# Pixracer_V1_FMU_Alternative_3.net
KiCad netlist of a schematic drawn in Altium Designer
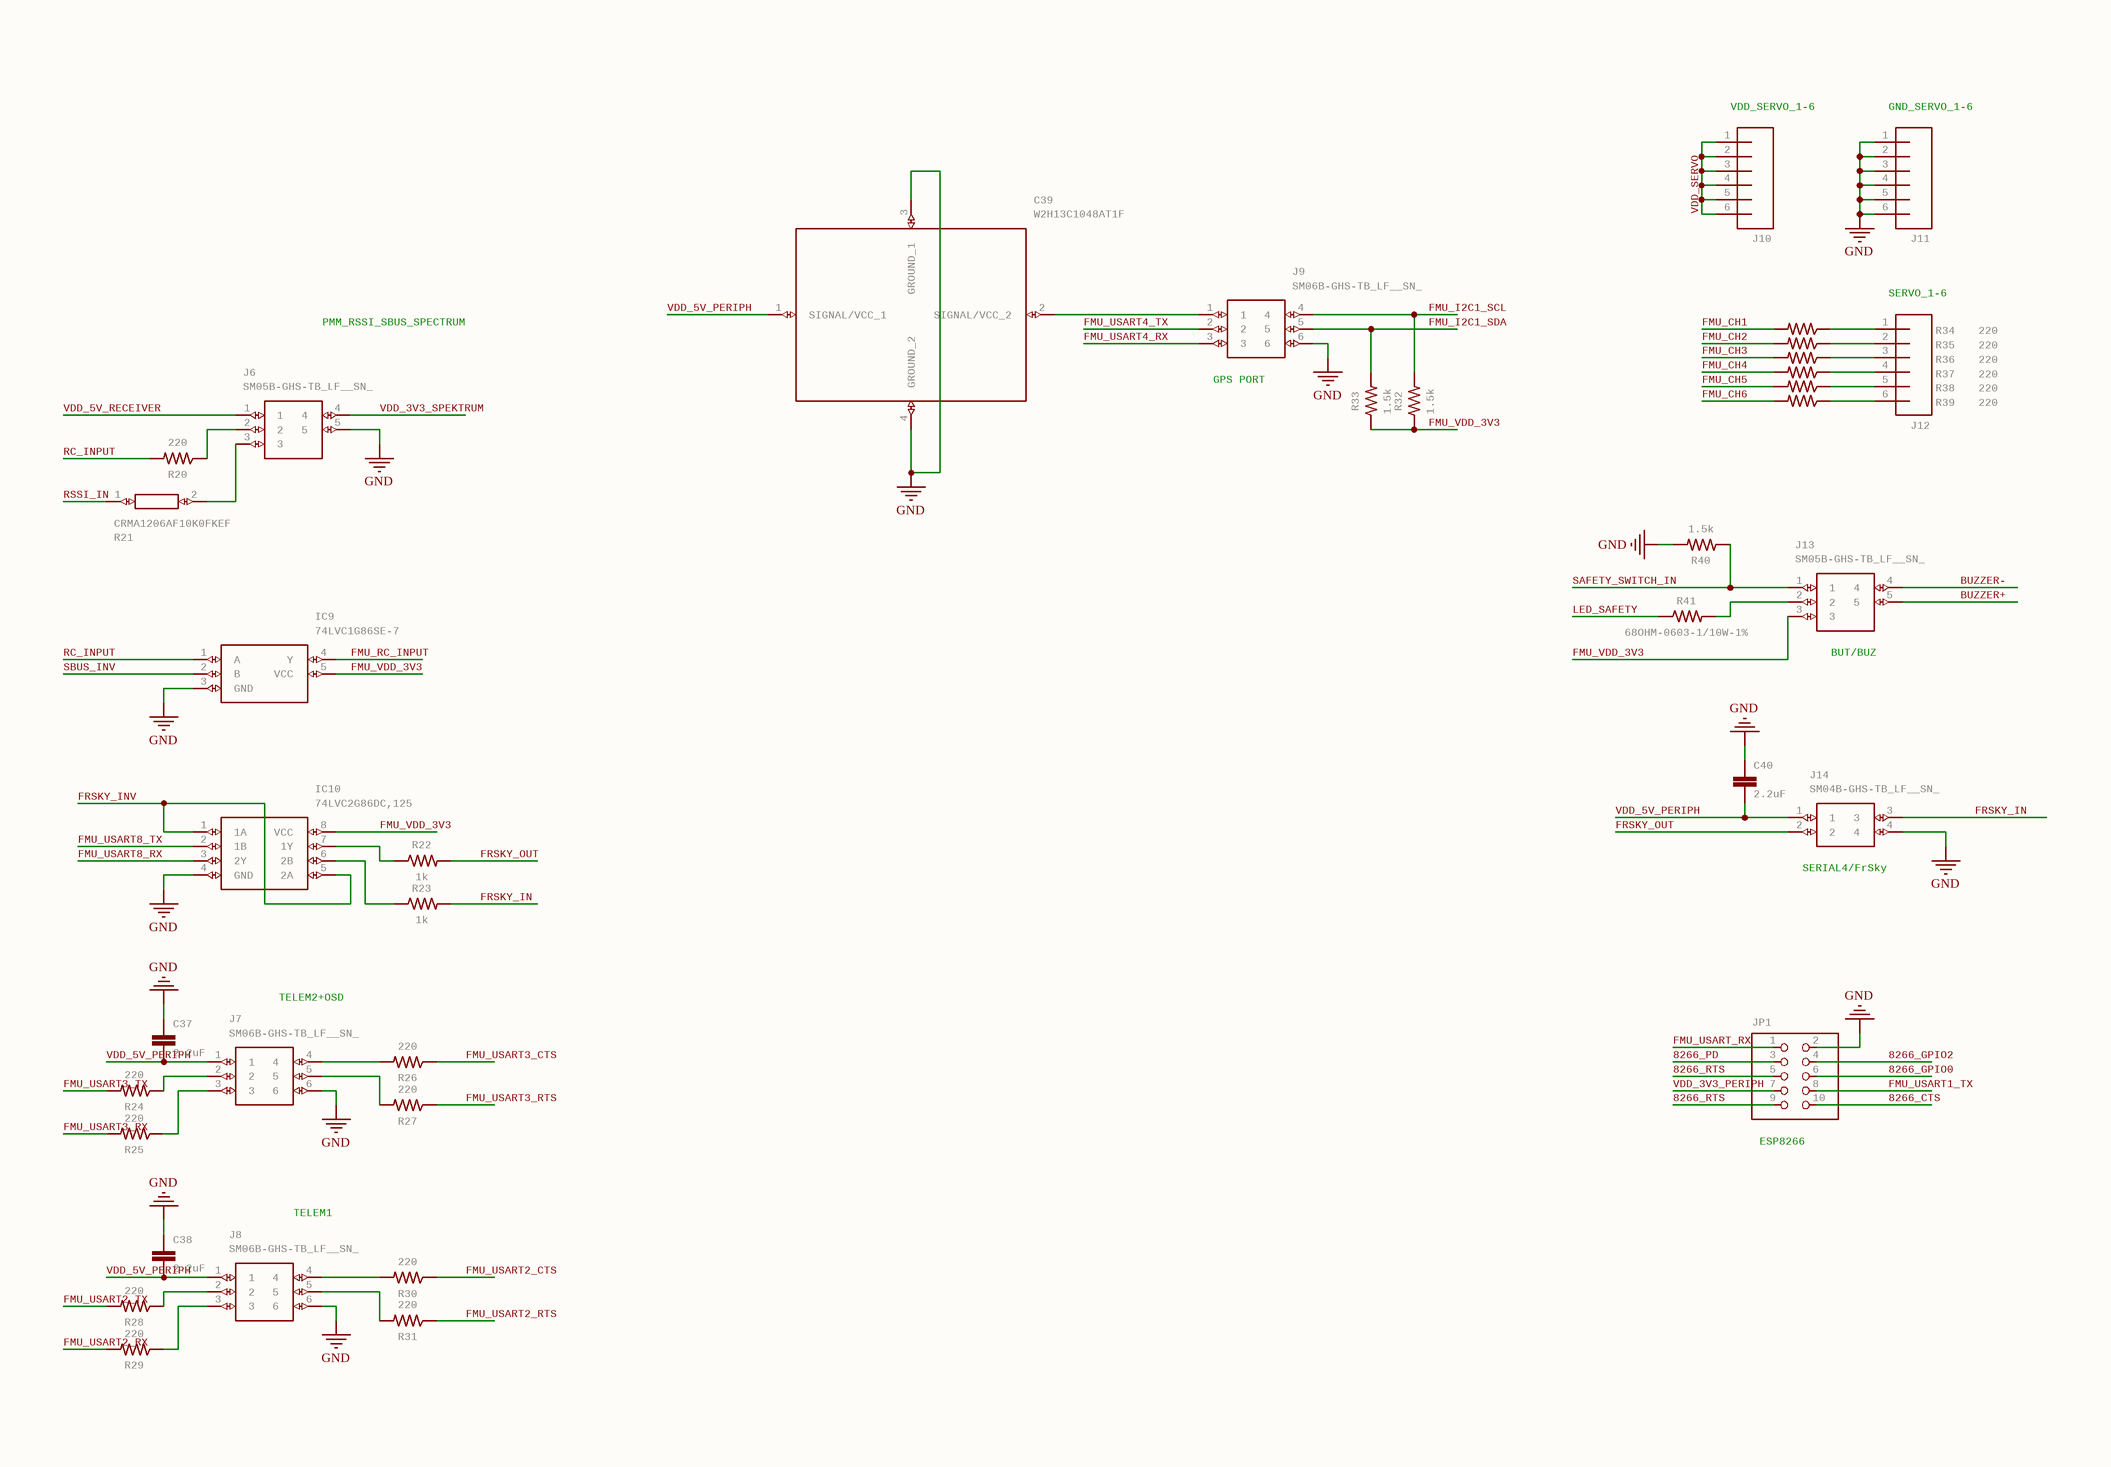
[diagram p0: Pixracer_V1_FMU_Alternative_3.SchDoc]

(export (version "E")
  (design (tool "Eeschema 10.0.6"))
  (components
    (comp (ref "C37")
      (value "2.2uF")
      (footprint "1206")
      (libsource (lib "SparkFun-Capacitors") (part "2.2UF-1206-50V-10%"))
    )
    (comp (ref "C38")
      (value "2.2uF")
      (footprint "1206")
      (libsource (lib "SparkFun-Capacitors") (part "2.2UF-1206-50V-10%"))
    )
    (comp (ref "C39")
      (value "W2H13C1048AT1F")
      (footprint "W2H13C1048AT1A")
      (description "Feed Through Capacitors 25volt 0.1uF X7R")
      (fields (field (name "MOUSER_PART_NUMBER") "581-W2H13C1048AT1F"))
      (libsource (lib "SamacSys_Parts") (part "W2H13C1048AT1F"))
    )
    (comp (ref "C40")
      (value "2.2uF")
      (footprint "1206")
      (libsource (lib "SparkFun-Capacitors") (part "2.2UF-1206-50V-10%"))
    )
    (comp (ref "IC9")
      (value "74LVC1G86SE-7")
      (footprint "SOT65P210X110-5N")
      (description "DiodesZetex 74LVC1G86SE-7, XOR 2 Input XOR, 1.65  5.5 V, 5-Pin SOT-353")
      (fields (field (name "MOUSER_PART_NUMBER") "621-74LVC1G86SE-7"))
      (libsource (lib "SamacSys_Parts") (part "74LVC1G86SE-7"))
    )
    (comp (ref "IC10")
      (value "74LVC2G86DC,125")
      (footprint "SOP50P310X100-8N")
      (description "74LVC2G86 - Dual 2-input EXCLUSIVE-OR gate")
      (fields (field (name "MOUSER_PART_NUMBER") "771-LVC2G86DC125"))
      (libsource (lib "SamacSys_Parts") (part "74LVC2G86DC,125"))
    )
    (comp (ref "J6")
      (value "SM05B-GHS-TB_LF__SN_")
      (footprint "SM05B-GHS-TB")
      (description "JST GH Series, 1.25mm Pitch 5 Way Right Angle PCB Header, Solder Termination, 1A")
      (fields
        (field (name "MANUFACTURER_PART_NUMBER") "SM05B-GHS-TB(LF)(SN)")
        (field (name "RS_PART_NUMBER") "7521807P")
      )
      (libsource (lib "SamacSys_Parts") (part "SM05B-GHS-TB_LF__SN_"))
    )
    (comp (ref "J7")
      (value "SM06B-GHS-TB_LF__SN_")
      (footprint "SM06B-GHS-TB")
      (fields
        (field (name "MANUFACTURER_PART_NUMBER") "SM06B-GHS-TB(LF)(SN)")
        (field (name "RS_PART_NUMBER") "7521800P")
      )
      (libsource (lib "SamacSys_Parts") (part "SM06B-GHS-TB_LF__SN_"))
    )
    (comp (ref "J8")
      (value "SM06B-GHS-TB_LF__SN_")
      (footprint "SM06B-GHS-TB")
      (fields
        (field (name "MANUFACTURER_PART_NUMBER") "SM06B-GHS-TB(LF)(SN)")
        (field (name "RS_PART_NUMBER") "7521800P")
      )
      (libsource (lib "SamacSys_Parts") (part "SM06B-GHS-TB_LF__SN_"))
    )
    (comp (ref "J9")
      (value "SM06B-GHS-TB_LF__SN_")
      (footprint "SM06B-GHS-TB")
      (fields
        (field (name "MANUFACTURER_PART_NUMBER") "SM06B-GHS-TB(LF)(SN)")
        (field (name "RS_PART_NUMBER") "7521800P")
      )
      (libsource (lib "SamacSys_Parts") (part "SM06B-GHS-TB_LF__SN_"))
    )
    (comp (ref "J10")
      (value "CONN_06NO_SILK_NO_POP")
      (footprint "1X06_NO_SILK")
      (libsource (lib "SparkFun-Connectors") (part "CONN_06NO_SILK_NO_POP"))
    )
    (comp (ref "J11")
      (value "CONN_06NO_SILK_NO_POP")
      (footprint "1X06_NO_SILK")
      (libsource (lib "SparkFun-Connectors") (part "CONN_06NO_SILK_NO_POP"))
    )
    (comp (ref "J12")
      (value "CONN_06NO_SILK_NO_POP")
      (footprint "1X06_NO_SILK")
      (libsource (lib "SparkFun-Connectors") (part "CONN_06NO_SILK_NO_POP"))
    )
    (comp (ref "J13")
      (value "SM05B-GHS-TB_LF__SN_")
      (footprint "SM05B-GHS-TB")
      (description "JST GH Series, 1.25mm Pitch 5 Way Right Angle PCB Header, Solder Termination, 1A")
      (fields
        (field (name "MANUFACTURER_PART_NUMBER") "SM05B-GHS-TB(LF)(SN)")
        (field (name "RS_PART_NUMBER") "7521807P")
      )
      (libsource (lib "SamacSys_Parts") (part "SM05B-GHS-TB_LF__SN_"))
    )
    (comp (ref "J14")
      (value "SM04B-GHS-TB_LF__SN_")
      (footprint "SM04B-GHS-TB")
      (description "JST GH Series, 1.25mm Pitch 4 Way Right Angle PCB Header, Solder Termination, 1A")
      (fields
        (field (name "MANUFACTURER_PART_NUMBER") "SM04B-GHS-TB(LF)(SN)")
        (field (name "RS_PART_NUMBER") "7521797P")
      )
      (libsource (lib "SamacSys_Parts") (part "SM04B-GHS-TB_LF__SN_"))
    )
    (comp (ref "JP1")
      (value "PINHD-2X5")
      (footprint "2X05")
      (description "PIN HEADER")
      (fields (field (name "LIBRARYNAME") "pinhead"))
      (libsource (lib "pinhead") (part "PINHD-2X5"))
    )
    (comp (ref "R20")
      (value "220")
      (footprint "0603")
      (libsource (lib "SparkFun-Resistors") (part "220OHM-0603-1/10W-1%"))
    )
    (comp (ref "R21")
      (value "CRMA1206AF10K0FKEF")
      (footprint "RESC3216X74N")
      (description "Thick Film Resistors - SMD 0.30W 10Kohm 1% AEC-Q200")
      (fields (field (name "MOUSER_PART_NUMBER") "71-CRMA1206AF10K0FKF"))
      (libsource (lib "SamacSys_Parts") (part "CRMA1206AF10K0FKEF"))
    )
    (comp (ref "R22")
      (value "1k")
      (footprint "0603")
      (libsource (lib "SparkFun-Resistors") (part "1KOHM-0603-1/10W-1%"))
    )
    (comp (ref "R23")
      (value "1k")
      (footprint "0603")
      (libsource (lib "SparkFun-Resistors") (part "1KOHM-0603-1/10W-1%"))
    )
    (comp (ref "R24")
      (value "220")
      (footprint "0603")
      (libsource (lib "SparkFun-Resistors") (part "220OHM-0603-1/10W-1%"))
    )
    (comp (ref "R25")
      (value "220")
      (footprint "0603")
      (libsource (lib "SparkFun-Resistors") (part "220OHM-0603-1/10W-1%"))
    )
    (comp (ref "R26")
      (value "220")
      (footprint "0603")
      (libsource (lib "SparkFun-Resistors") (part "220OHM-0603-1/10W-1%"))
    )
    (comp (ref "R27")
      (value "220")
      (footprint "0603")
      (libsource (lib "SparkFun-Resistors") (part "220OHM-0603-1/10W-1%"))
    )
    (comp (ref "R28")
      (value "220")
      (footprint "0603")
      (libsource (lib "SparkFun-Resistors") (part "220OHM-0603-1/10W-1%"))
    )
    (comp (ref "R29")
      (value "220")
      (footprint "0603")
      (libsource (lib "SparkFun-Resistors") (part "220OHM-0603-1/10W-1%"))
    )
    (comp (ref "R30")
      (value "220")
      (footprint "0603")
      (libsource (lib "SparkFun-Resistors") (part "220OHM-0603-1/10W-1%"))
    )
    (comp (ref "R31")
      (value "220")
      (footprint "0603")
      (libsource (lib "SparkFun-Resistors") (part "220OHM-0603-1/10W-1%"))
    )
    (comp (ref "R32")
      (value "1.5k")
      (footprint "0603")
      (libsource (lib "SparkFun-Resistors") (part "1.5KOHM-0603-1/10W-1%"))
    )
    (comp (ref "R33")
      (value "1.5k")
      (footprint "0603")
      (libsource (lib "SparkFun-Resistors") (part "1.5KOHM-0603-1/10W-1%"))
    )
    (comp (ref "R34")
      (value "220")
      (footprint "0603")
      (libsource (lib "SparkFun-Resistors") (part "220OHM-0603-1/10W-1%"))
    )
    (comp (ref "R35")
      (value "220")
      (footprint "0603")
      (libsource (lib "SparkFun-Resistors") (part "220OHM-0603-1/10W-1%"))
    )
    (comp (ref "R36")
      (value "220")
      (footprint "0603")
      (libsource (lib "SparkFun-Resistors") (part "220OHM-0603-1/10W-1%"))
    )
    (comp (ref "R37")
      (value "220")
      (footprint "0603")
      (libsource (lib "SparkFun-Resistors") (part "220OHM-0603-1/10W-1%"))
    )
    (comp (ref "R38")
      (value "220")
      (footprint "0603")
      (libsource (lib "SparkFun-Resistors") (part "220OHM-0603-1/10W-1%"))
    )
    (comp (ref "R39")
      (value "220")
      (footprint "0603")
      (libsource (lib "SparkFun-Resistors") (part "220OHM-0603-1/10W-1%"))
    )
    (comp (ref "R40")
      (value "1.5k")
      (footprint "0603")
      (libsource (lib "SparkFun-Resistors") (part "1.5KOHM-0603-1/10W-1%"))
    )
    (comp (ref "R41")
      (value "68OHM-0603-1/10W-1%")
      (footprint "0603")
      (libsource (lib "SparkFun-Resistors") (part "68OHM-0603-1/10W-1%"))
    )
  )
  (nets
    (net (code "1") (name "/8266_CTS") (class "Default")
      (node (ref "JP1") (pin "10") (pinfunction "10_10") (pintype "passive"))
    )
    (net (code "2") (name "/8266_GPIO0") (class "Default")
      (node (ref "JP1") (pin "6") (pinfunction "6_6") (pintype "passive"))
    )
    (net (code "3") (name "/8266_GPIO2") (class "Default")
      (node (ref "JP1") (pin "4") (pinfunction "4_4") (pintype "passive"))
    )
    (net (code "4") (name "/8266_PD") (class "Default")
      (node (ref "JP1") (pin "3") (pinfunction "3_3") (pintype "passive"))
    )
    (net (code "5") (name "/8266_RTS") (class "Default")
      (node (ref "JP1") (pin "5") (pinfunction "5_5") (pintype "passive"))
      (node (ref "JP1") (pin "9") (pinfunction "9_9") (pintype "passive"))
    )
    (net (code "6") (name "/BUZZER+") (class "Default")
      (node (ref "J13") (pin "5") (pinfunction "5_5") (pintype "bidirectional"))
    )
    (net (code "7") (name "/BUZZER-") (class "Default")
      (node (ref "J13") (pin "4") (pinfunction "4_4") (pintype "bidirectional"))
    )
    (net (code "8") (name "/FMU_CH1") (class "Default")
      (node (ref "R34") (pin "2") (pinfunction "2_2") (pintype "passive"))
    )
    (net (code "9") (name "/FMU_CH2") (class "Default")
      (node (ref "R35") (pin "2") (pinfunction "2_2") (pintype "passive"))
    )
    (net (code "10") (name "/FMU_CH3") (class "Default")
      (node (ref "R36") (pin "2") (pinfunction "2_2") (pintype "passive"))
    )
    (net (code "11") (name "/FMU_CH4") (class "Default")
      (node (ref "R37") (pin "2") (pinfunction "2_2") (pintype "passive"))
    )
    (net (code "12") (name "/FMU_CH5") (class "Default")
      (node (ref "R38") (pin "2") (pinfunction "2_2") (pintype "passive"))
    )
    (net (code "13") (name "/FMU_CH6") (class "Default")
      (node (ref "R39") (pin "2") (pinfunction "2_2") (pintype "passive"))
    )
    (net (code "14") (name "/FMU_I2C1_SCL") (class "Default")
      (node (ref "J9") (pin "4") (pinfunction "4_4") (pintype "bidirectional"))
      (node (ref "R32") (pin "2") (pinfunction "2_2") (pintype "passive"))
    )
    (net (code "15") (name "/FMU_I2C1_SDA") (class "Default")
      (node (ref "J9") (pin "5") (pinfunction "5_5") (pintype "bidirectional"))
      (node (ref "R33") (pin "2") (pinfunction "2_2") (pintype "passive"))
    )
    (net (code "16") (name "/FMU_RC_INPUT") (class "Default")
      (node (ref "IC9") (pin "4") (pinfunction "Y_4") (pintype "bidirectional"))
    )
    (net (code "17") (name "/FMU_USART1_TX") (class "Default")
      (node (ref "JP1") (pin "8") (pinfunction "8_8") (pintype "passive"))
    )
    (net (code "18") (name "/FMU_USART2_CTS") (class "Default")
      (node (ref "R30") (pin "1") (pinfunction "1_1") (pintype "passive"))
    )
    (net (code "19") (name "/FMU_USART2_RTS") (class "Default")
      (node (ref "R31") (pin "1") (pinfunction "1_1") (pintype "passive"))
    )
    (net (code "20") (name "/FMU_USART2_RX") (class "Default")
      (node (ref "R29") (pin "2") (pinfunction "2_2") (pintype "passive"))
    )
    (net (code "21") (name "/FMU_USART2_TX") (class "Default")
      (node (ref "R28") (pin "2") (pinfunction "2_2") (pintype "passive"))
    )
    (net (code "22") (name "/FMU_USART3_CTS") (class "Default")
      (node (ref "R26") (pin "1") (pinfunction "1_1") (pintype "passive"))
    )
    (net (code "23") (name "/FMU_USART3_RTS") (class "Default")
      (node (ref "R27") (pin "1") (pinfunction "1_1") (pintype "passive"))
    )
    (net (code "24") (name "/FMU_USART3_RX") (class "Default")
      (node (ref "R25") (pin "2") (pinfunction "2_2") (pintype "passive"))
    )
    (net (code "25") (name "/FMU_USART3_TX") (class "Default")
      (node (ref "R24") (pin "2") (pinfunction "2_2") (pintype "passive"))
    )
    (net (code "26") (name "/FMU_USART4_RX") (class "Default")
      (node (ref "J9") (pin "3") (pinfunction "3_3") (pintype "bidirectional"))
    )
    (net (code "27") (name "/FMU_USART4_TX") (class "Default")
      (node (ref "J9") (pin "2") (pinfunction "2_2") (pintype "bidirectional"))
    )
    (net (code "28") (name "/FMU_USART8_RX") (class "Default")
      (node (ref "IC10") (pin "3") (pinfunction "2Y_3") (pintype "bidirectional"))
    )
    (net (code "29") (name "/FMU_USART8_TX") (class "Default")
      (node (ref "IC10") (pin "2") (pinfunction "1B_2") (pintype "bidirectional"))
    )
    (net (code "30") (name "/FMU_USART_RX") (class "Default")
      (node (ref "JP1") (pin "1") (pinfunction "1_1") (pintype "passive"))
    )
    (net (code "31") (name "/FMU_VDD_3V3") (class "Default")
      (node (ref "IC10") (pin "8") (pinfunction "VCC_8") (pintype "bidirectional"))
      (node (ref "IC9") (pin "5") (pinfunction "VCC_5") (pintype "bidirectional"))
      (node (ref "J13") (pin "3") (pinfunction "3_3") (pintype "bidirectional"))
      (node (ref "R32") (pin "1") (pinfunction "1_1") (pintype "passive"))
      (node (ref "R33") (pin "1") (pinfunction "1_1") (pintype "passive"))
    )
    (net (code "32") (name "/FRSKY_IN") (class "Default")
      (node (ref "J14") (pin "3") (pinfunction "3_3") (pintype "bidirectional"))
      (node (ref "R23") (pin "2") (pinfunction "2_2") (pintype "passive"))
    )
    (net (code "33") (name "/FRSKY_INV") (class "Default")
      (node (ref "IC10") (pin "1") (pinfunction "1A_1") (pintype "bidirectional"))
      (node (ref "IC10") (pin "5") (pinfunction "2A_5") (pintype "bidirectional"))
    )
    (net (code "34") (name "/FRSKY_OUT") (class "Default")
      (node (ref "J14") (pin "2") (pinfunction "2_2") (pintype "bidirectional"))
      (node (ref "R22") (pin "2") (pinfunction "2_2") (pintype "passive"))
    )
    (net (code "35") (name "/LED_SAFETY") (class "Default")
      (node (ref "R41") (pin "1") (pinfunction "1_1") (pintype "passive"))
    )
    (net (code "36") (name "/RC_INPUT") (class "Default")
      (node (ref "IC9") (pin "1") (pinfunction "A_1") (pintype "bidirectional"))
      (node (ref "R20") (pin "2") (pinfunction "2_2") (pintype "passive"))
    )
    (net (code "37") (name "/RSSI_IN") (class "Default")
      (node (ref "R21") (pin "1") (pinfunction "1_1") (pintype "bidirectional"))
    )
    (net (code "38") (name "/SAFETY_SWITCH_IN") (class "Default")
      (node (ref "J13") (pin "1") (pinfunction "1_1") (pintype "bidirectional"))
      (node (ref "R40") (pin "1") (pinfunction "1_1") (pintype "passive"))
    )
    (net (code "39") (name "/SBUS_INV") (class "Default")
      (node (ref "IC9") (pin "2") (pinfunction "B_2") (pintype "bidirectional"))
    )
    (net (code "40") (name "/VDD_3V3_PERIPH") (class "Default")
      (node (ref "JP1") (pin "7") (pinfunction "7_7") (pintype "passive"))
    )
    (net (code "41") (name "/VDD_3V3_SPEKTRUM") (class "Default")
      (node (ref "J6") (pin "4") (pinfunction "4_4") (pintype "bidirectional"))
    )
    (net (code "42") (name "/VDD_5V_PERIPH") (class "Default")
      (node (ref "C37") (pin "2") (pinfunction "2_2") (pintype "passive"))
      (node (ref "C38") (pin "2") (pinfunction "2_2") (pintype "passive"))
      (node (ref "C39") (pin "1") (pinfunction "SIGNAL/VCC_1_1") (pintype "bidirectional"))
      (node (ref "C40") (pin "2") (pinfunction "2_2") (pintype "passive"))
      (node (ref "J14") (pin "1") (pinfunction "1_1") (pintype "bidirectional"))
      (node (ref "J7") (pin "1") (pinfunction "1_1") (pintype "bidirectional"))
      (node (ref "J8") (pin "1") (pinfunction "1_1") (pintype "bidirectional"))
    )
    (net (code "43") (name "/VDD_5V_RECEIVER") (class "Default")
      (node (ref "J6") (pin "1") (pinfunction "1_1") (pintype "bidirectional"))
    )
    (net (code "44") (name "/VDD_SERVO") (class "Default")
      (node (ref "J10") (pin "1") (pinfunction "1_1") (pintype "passive"))
      (node (ref "J10") (pin "2") (pinfunction "2_2") (pintype "passive"))
      (node (ref "J10") (pin "3") (pinfunction "3_3") (pintype "passive"))
      (node (ref "J10") (pin "4") (pinfunction "4_4") (pintype "passive"))
      (node (ref "J10") (pin "5") (pinfunction "5_5") (pintype "passive"))
      (node (ref "J10") (pin "6") (pinfunction "6_6") (pintype "passive"))
    )
    (net (code "45") (name "GND") (class "Default")
      (node (ref "C37") (pin "1") (pinfunction "1_1") (pintype "passive"))
      (node (ref "C38") (pin "1") (pinfunction "1_1") (pintype "passive"))
      (node (ref "C39") (pin "3") (pinfunction "GROUND_1_3") (pintype "bidirectional"))
      (node (ref "C39") (pin "4") (pinfunction "GROUND_2_4") (pintype "bidirectional"))
      (node (ref "C40") (pin "1") (pinfunction "1_1") (pintype "passive"))
      (node (ref "IC10") (pin "4") (pinfunction "GND_4") (pintype "bidirectional"))
      (node (ref "IC9") (pin "3") (pinfunction "GND_3") (pintype "bidirectional"))
      (node (ref "J11") (pin "1") (pinfunction "1_1") (pintype "passive"))
      (node (ref "J11") (pin "2") (pinfunction "2_2") (pintype "passive"))
      (node (ref "J11") (pin "3") (pinfunction "3_3") (pintype "passive"))
      (node (ref "J11") (pin "4") (pinfunction "4_4") (pintype "passive"))
      (node (ref "J11") (pin "5") (pinfunction "5_5") (pintype "passive"))
      (node (ref "J11") (pin "6") (pinfunction "6_6") (pintype "passive"))
      (node (ref "J14") (pin "4") (pinfunction "4_4") (pintype "bidirectional"))
      (node (ref "J6") (pin "5") (pinfunction "5_5") (pintype "bidirectional"))
      (node (ref "J7") (pin "6") (pinfunction "6_6") (pintype "bidirectional"))
      (node (ref "J8") (pin "6") (pinfunction "6_6") (pintype "bidirectional"))
      (node (ref "J9") (pin "6") (pinfunction "6_6") (pintype "bidirectional"))
      (node (ref "JP1") (pin "2") (pinfunction "2_2") (pintype "passive"))
      (node (ref "R40") (pin "2") (pinfunction "2_2") (pintype "passive"))
    )
    (net (code "46") (name "Net-(C39-SIGNAL{slash}VCC_2)") (class "Default")
      (node (ref "C39") (pin "2") (pinfunction "SIGNAL/VCC_2_2") (pintype "bidirectional"))
      (node (ref "J9") (pin "1") (pinfunction "1_1") (pintype "bidirectional"))
    )
    (net (code "47") (name "Net-(IC10-1Y)") (class "Default")
      (node (ref "IC10") (pin "7") (pinfunction "1Y_7") (pintype "bidirectional"))
      (node (ref "R22") (pin "1") (pinfunction "1_1") (pintype "passive"))
    )
    (net (code "48") (name "Net-(IC10-2B)") (class "Default")
      (node (ref "IC10") (pin "6") (pinfunction "2B_6") (pintype "bidirectional"))
      (node (ref "R23") (pin "1") (pinfunction "1_1") (pintype "passive"))
    )
    (net (code "49") (name "Net-(J6-Pad2)") (class "Default")
      (node (ref "J6") (pin "2") (pinfunction "2_2") (pintype "bidirectional"))
      (node (ref "R20") (pin "1") (pinfunction "1_1") (pintype "passive"))
    )
    (net (code "50") (name "Net-(J6-Pad3)") (class "Default")
      (node (ref "J6") (pin "3") (pinfunction "3_3") (pintype "bidirectional"))
      (node (ref "R21") (pin "2") (pinfunction "2_2") (pintype "bidirectional"))
    )
    (net (code "51") (name "Net-(J7-Pad2)") (class "Default")
      (node (ref "J7") (pin "2") (pinfunction "2_2") (pintype "bidirectional"))
      (node (ref "R24") (pin "1") (pinfunction "1_1") (pintype "passive"))
    )
    (net (code "52") (name "Net-(J7-Pad3)") (class "Default")
      (node (ref "J7") (pin "3") (pinfunction "3_3") (pintype "bidirectional"))
      (node (ref "R25") (pin "1") (pinfunction "1_1") (pintype "passive"))
    )
    (net (code "53") (name "Net-(J7-Pad4)") (class "Default")
      (node (ref "J7") (pin "4") (pinfunction "4_4") (pintype "bidirectional"))
      (node (ref "R26") (pin "2") (pinfunction "2_2") (pintype "passive"))
    )
    (net (code "54") (name "Net-(J7-Pad5)") (class "Default")
      (node (ref "J7") (pin "5") (pinfunction "5_5") (pintype "bidirectional"))
      (node (ref "R27") (pin "2") (pinfunction "2_2") (pintype "passive"))
    )
    (net (code "55") (name "Net-(J8-Pad2)") (class "Default")
      (node (ref "J8") (pin "2") (pinfunction "2_2") (pintype "bidirectional"))
      (node (ref "R28") (pin "1") (pinfunction "1_1") (pintype "passive"))
    )
    (net (code "56") (name "Net-(J8-Pad3)") (class "Default")
      (node (ref "J8") (pin "3") (pinfunction "3_3") (pintype "bidirectional"))
      (node (ref "R29") (pin "1") (pinfunction "1_1") (pintype "passive"))
    )
    (net (code "57") (name "Net-(J8-Pad4)") (class "Default")
      (node (ref "J8") (pin "4") (pinfunction "4_4") (pintype "bidirectional"))
      (node (ref "R30") (pin "2") (pinfunction "2_2") (pintype "passive"))
    )
    (net (code "58") (name "Net-(J8-Pad5)") (class "Default")
      (node (ref "J8") (pin "5") (pinfunction "5_5") (pintype "bidirectional"))
      (node (ref "R31") (pin "2") (pinfunction "2_2") (pintype "passive"))
    )
    (net (code "59") (name "Net-(J12-Pad1)") (class "Default")
      (node (ref "J12") (pin "1") (pinfunction "1_1") (pintype "passive"))
      (node (ref "R34") (pin "1") (pinfunction "1_1") (pintype "passive"))
    )
    (net (code "60") (name "Net-(J12-Pad2)") (class "Default")
      (node (ref "J12") (pin "2") (pinfunction "2_2") (pintype "passive"))
      (node (ref "R35") (pin "1") (pinfunction "1_1") (pintype "passive"))
    )
    (net (code "61") (name "Net-(J12-Pad3)") (class "Default")
      (node (ref "J12") (pin "3") (pinfunction "3_3") (pintype "passive"))
      (node (ref "R36") (pin "1") (pinfunction "1_1") (pintype "passive"))
    )
    (net (code "62") (name "Net-(J12-Pad4)") (class "Default")
      (node (ref "J12") (pin "4") (pinfunction "4_4") (pintype "passive"))
      (node (ref "R37") (pin "1") (pinfunction "1_1") (pintype "passive"))
    )
    (net (code "63") (name "Net-(J12-Pad5)") (class "Default")
      (node (ref "J12") (pin "5") (pinfunction "5_5") (pintype "passive"))
      (node (ref "R38") (pin "1") (pinfunction "1_1") (pintype "passive"))
    )
    (net (code "64") (name "Net-(J12-Pad6)") (class "Default")
      (node (ref "J12") (pin "6") (pinfunction "6_6") (pintype "passive"))
      (node (ref "R39") (pin "1") (pinfunction "1_1") (pintype "passive"))
    )
    (net (code "65") (name "Net-(J13-Pad2)") (class "Default")
      (node (ref "J13") (pin "2") (pinfunction "2_2") (pintype "bidirectional"))
      (node (ref "R41") (pin "2") (pinfunction "2_2") (pintype "passive"))
    )
  )
)
